# LED_Limiter.net
KiCad netlist of a schematic drawn in EAGLE
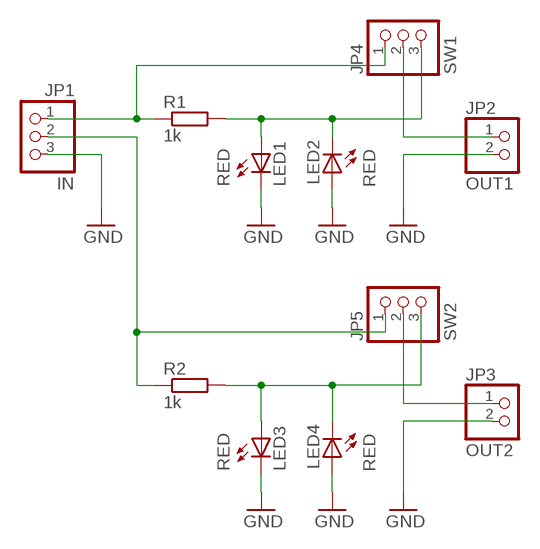
[diagram p0: schematic, sheet 1]

(export (version "E")
  (design (tool "Eeschema 10.0.6"))
  (components
    (comp (ref "JP1")
      (value "IN")
      (footprint "eagle-import:1X03")
      (libsource (lib "eagle-import") (part "PINHD-1X3"))
    )
    (comp (ref "JP2")
      (value "OUT1")
      (footprint "eagle-import:1X02")
      (libsource (lib "eagle-import") (part "PINHD-1X2"))
    )
    (comp (ref "JP3")
      (value "OUT2")
      (footprint "eagle-import:1X02")
      (libsource (lib "eagle-import") (part "PINHD-1X2"))
    )
    (comp (ref "JP4")
      (value "SW1")
      (footprint "eagle-import:1X03")
      (libsource (lib "eagle-import") (part "PINHD-1X3"))
    )
    (comp (ref "JP5")
      (value "SW2")
      (footprint "eagle-import:1X03")
      (libsource (lib "eagle-import") (part "PINHD-1X3"))
    )
    (comp (ref "LED1")
      (value "RED")
      (footprint "eagle-import:LED3MM")
      (libsource (lib "eagle-import") (part "LED3MM"))
    )
    (comp (ref "LED2")
      (value "RED")
      (footprint "eagle-import:LED3MM")
      (libsource (lib "eagle-import") (part "LED3MM"))
    )
    (comp (ref "LED3")
      (value "RED")
      (footprint "eagle-import:LED3MM")
      (libsource (lib "eagle-import") (part "LED3MM"))
    )
    (comp (ref "LED4")
      (value "RED")
      (footprint "eagle-import:LED3MM")
      (libsource (lib "eagle-import") (part "LED3MM"))
    )
    (comp (ref "R1")
      (value "1k")
      (footprint "eagle-import:0207_7")
      (libsource (lib "eagle-import") (part "R-EU_0207/7"))
    )
    (comp (ref "R2")
      (value "1k")
      (footprint "eagle-import:0207_7")
      (libsource (lib "eagle-import") (part "R-EU_0207/7"))
    )
  )
  (nets
    (net (code "1") (name "GND") (class "Default")
      (node (ref "JP1") (pin "3") (pinfunction "3_3") (pintype "passive"))
      (node (ref "JP2") (pin "2") (pinfunction "2_2") (pintype "passive"))
      (node (ref "JP3") (pin "2") (pinfunction "2_2") (pintype "passive"))
      (node (ref "LED1") (pin "K") (pinfunction "C_K") (pintype "passive"))
      (node (ref "LED2") (pin "A") (pinfunction "A_A") (pintype "passive"))
      (node (ref "LED3") (pin "K") (pinfunction "C_K") (pintype "passive"))
      (node (ref "LED4") (pin "A") (pinfunction "A_A") (pintype "passive"))
    )
    (net (code "2") (name "Net-(JP1-Pad1)") (class "Default")
      (node (ref "JP1") (pin "1") (pinfunction "1_1") (pintype "passive"))
      (node (ref "JP4") (pin "1") (pinfunction "1_1") (pintype "passive"))
      (node (ref "R1") (pin "1") (pinfunction "1_1") (pintype "passive"))
    )
    (net (code "3") (name "Net-(JP1-Pad2)") (class "Default")
      (node (ref "JP1") (pin "2") (pinfunction "2_2") (pintype "passive"))
      (node (ref "JP5") (pin "1") (pinfunction "1_1") (pintype "passive"))
      (node (ref "R2") (pin "1") (pinfunction "1_1") (pintype "passive"))
    )
    (net (code "4") (name "Net-(JP2-Pad1)") (class "Default")
      (node (ref "JP2") (pin "1") (pinfunction "1_1") (pintype "passive"))
      (node (ref "JP4") (pin "2") (pinfunction "2_2") (pintype "passive"))
    )
    (net (code "5") (name "Net-(JP3-Pad1)") (class "Default")
      (node (ref "JP3") (pin "1") (pinfunction "1_1") (pintype "passive"))
      (node (ref "JP5") (pin "2") (pinfunction "2_2") (pintype "passive"))
    )
    (net (code "6") (name "Net-(LED2-C)") (class "Default")
      (node (ref "JP4") (pin "3") (pinfunction "3_3") (pintype "passive"))
      (node (ref "LED1") (pin "A") (pinfunction "A_A") (pintype "passive"))
      (node (ref "LED2") (pin "K") (pinfunction "C_K") (pintype "passive"))
      (node (ref "R1") (pin "2") (pinfunction "2_2") (pintype "passive"))
    )
    (net (code "7") (name "Net-(LED4-C)") (class "Default")
      (node (ref "JP5") (pin "3") (pinfunction "3_3") (pintype "passive"))
      (node (ref "LED3") (pin "A") (pinfunction "A_A") (pintype "passive"))
      (node (ref "LED4") (pin "K") (pinfunction "C_K") (pintype "passive"))
      (node (ref "R2") (pin "2") (pinfunction "2_2") (pintype "passive"))
    )
  )
)
